# max1k.net
KiCad netlist of a schematic drawn in EAGLE
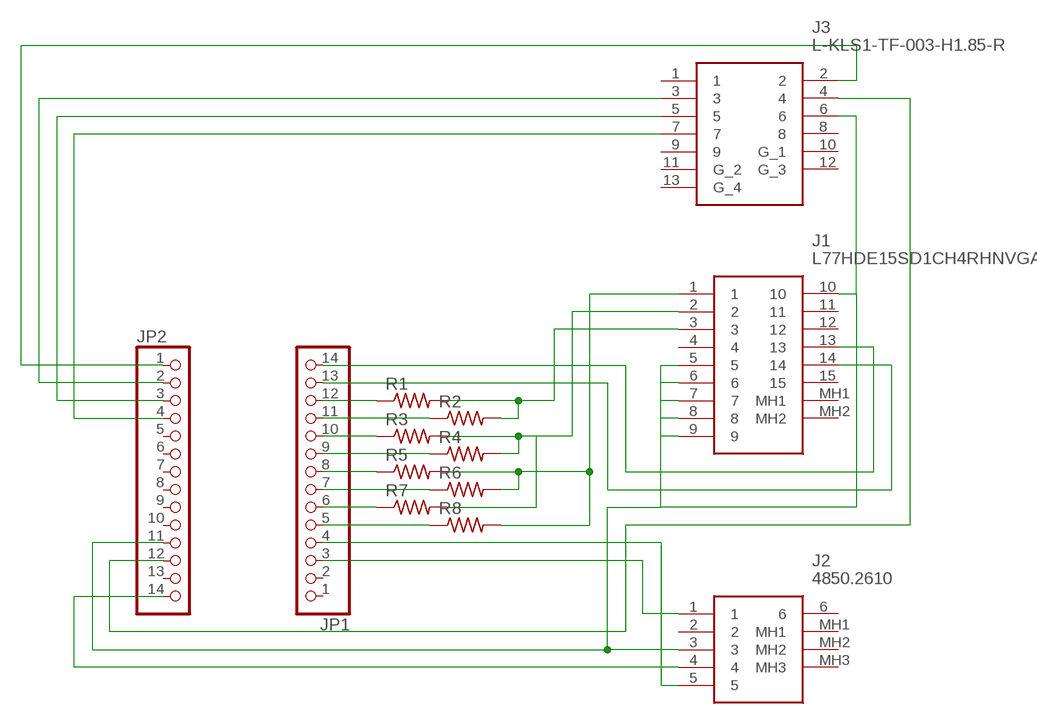
[diagram p0: schematic, sheet 1]

(export (version "E")
  (design (tool "Eeschema 10.0.6"))
  (components
    (comp (ref "J1")
      (value "L77HDE15SD1CH4RHNVGA")
      (footprint "eagle-import:L77HDE15SD1CH4RHNVGA")
      (fields (field (name "MOUSER_PART_NUMBER") "523-7HDE15SDH4RHNVGA"))
      (libsource (lib "eagle-import") (part "L77HDE15SD1CH4RHNVGA"))
    )
    (comp (ref "J2")
      (value "4850.2610")
      (footprint "eagle-import:48502610")
      (fields (field (name "MOUSER_PART_NUMBER") "693-4850.2610"))
      (libsource (lib "eagle-import") (part "4850.2610"))
    )
    (comp (ref "J3")
      (value "L-KLS1-TF-003-H1.85-R")
      (footprint "eagle-import:L-KLS1-TF-003-H1.85-R")
      (libsource (lib "eagle-import") (part "L-KLS1-TF-003-H1.85-R"))
    )
    (comp (ref "JP1")
      (value "PINHD-1X14-CB")
      (footprint "eagle-import:1X14-CB")
      (libsource (lib "eagle-import") (part "PINHD-1X14-CB"))
    )
    (comp (ref "JP2")
      (value "PINHD-1X14-CB")
      (footprint "eagle-import:1X14-CB")
      (libsource (lib "eagle-import") (part "PINHD-1X14-CB"))
    )
    (comp (ref "R1")
      (value "R-US_R0805")
      (footprint "eagle-import:R0805")
      (libsource (lib "eagle-import") (part "R-US_R0805"))
    )
    (comp (ref "R2")
      (value "R-US_R0805")
      (footprint "eagle-import:R0805")
      (libsource (lib "eagle-import") (part "R-US_R0805"))
    )
    (comp (ref "R3")
      (value "R-US_R0805")
      (footprint "eagle-import:R0805")
      (libsource (lib "eagle-import") (part "R-US_R0805"))
    )
    (comp (ref "R4")
      (value "R-US_R0805")
      (footprint "eagle-import:R0805")
      (libsource (lib "eagle-import") (part "R-US_R0805"))
    )
    (comp (ref "R5")
      (value "R-US_R0805")
      (footprint "eagle-import:R0805")
      (libsource (lib "eagle-import") (part "R-US_R0805"))
    )
    (comp (ref "R6")
      (value "R-US_R0805")
      (footprint "eagle-import:R0805")
      (libsource (lib "eagle-import") (part "R-US_R0805"))
    )
    (comp (ref "R7")
      (value "R-US_R0805")
      (footprint "eagle-import:R0805")
      (libsource (lib "eagle-import") (part "R-US_R0805"))
    )
    (comp (ref "R8")
      (value "R-US_R0805")
      (footprint "eagle-import:R0805")
      (libsource (lib "eagle-import") (part "R-US_R0805"))
    )
  )
  (nets
    (net (code "1") (name "Net-(J1-Pad1)") (class "Default")
      (node (ref "J1") (pin "1") (pinfunction "1_1") (pintype "bidirectional"))
      (node (ref "R5") (pin "2") (pinfunction "2_2") (pintype "passive"))
      (node (ref "R6") (pin "2") (pinfunction "2_2") (pintype "passive"))
      (node (ref "R8") (pin "2") (pinfunction "2_2") (pintype "passive"))
    )
    (net (code "2") (name "Net-(J1-Pad2)") (class "Default")
      (node (ref "J1") (pin "2") (pinfunction "2_2") (pintype "bidirectional"))
      (node (ref "R3") (pin "2") (pinfunction "2_2") (pintype "passive"))
      (node (ref "R4") (pin "2") (pinfunction "2_2") (pintype "passive"))
      (node (ref "R7") (pin "2") (pinfunction "2_2") (pintype "passive"))
    )
    (net (code "3") (name "Net-(J1-Pad3)") (class "Default")
      (node (ref "J1") (pin "3") (pinfunction "3_3") (pintype "bidirectional"))
      (node (ref "R1") (pin "2") (pinfunction "2_2") (pintype "passive"))
      (node (ref "R2") (pin "2") (pinfunction "2_2") (pintype "passive"))
    )
    (net (code "4") (name "Net-(J1-Pad10)") (class "Default")
      (node (ref "J1") (pin "10") (pinfunction "10_10") (pintype "bidirectional"))
      (node (ref "J1") (pin "5") (pinfunction "5_5") (pintype "bidirectional"))
      (node (ref "J1") (pin "6") (pinfunction "6_6") (pintype "bidirectional"))
      (node (ref "J1") (pin "7") (pinfunction "7_7") (pintype "bidirectional"))
      (node (ref "J1") (pin "8") (pinfunction "8_8") (pintype "bidirectional"))
      (node (ref "J1") (pin "9") (pinfunction "9_9") (pintype "bidirectional"))
      (node (ref "J2") (pin "3") (pinfunction "3_3") (pintype "bidirectional"))
      (node (ref "J3") (pin "6") (pinfunction "6_6") (pintype "bidirectional"))
      (node (ref "JP2") (pin "11") (pinfunction "11_11") (pintype "passive"))
    )
    (net (code "5") (name "Net-(J1-Pad13)") (class "Default")
      (node (ref "J1") (pin "13") (pinfunction "13_13") (pintype "bidirectional"))
      (node (ref "JP1") (pin "14") (pinfunction "14_14") (pintype "passive"))
    )
    (net (code "6") (name "Net-(J1-Pad14)") (class "Default")
      (node (ref "J1") (pin "14") (pinfunction "14_14") (pintype "bidirectional"))
      (node (ref "JP1") (pin "13") (pinfunction "13_13") (pintype "passive"))
    )
    (net (code "7") (name "Net-(J2-Pad1)") (class "Default")
      (node (ref "J2") (pin "1") (pinfunction "1_1") (pintype "bidirectional"))
      (node (ref "JP1") (pin "3") (pinfunction "3_3") (pintype "passive"))
    )
    (net (code "8") (name "Net-(J2-Pad4)") (class "Default")
      (node (ref "J2") (pin "4") (pinfunction "4_4") (pintype "bidirectional"))
      (node (ref "JP2") (pin "14") (pinfunction "14_14") (pintype "passive"))
    )
    (net (code "9") (name "Net-(J2-Pad5)") (class "Default")
      (node (ref "J2") (pin "5") (pinfunction "5_5") (pintype "bidirectional"))
      (node (ref "JP1") (pin "4") (pinfunction "4_4") (pintype "passive"))
    )
    (net (code "10") (name "Net-(J3-Pad2)") (class "Default")
      (node (ref "J3") (pin "2") (pinfunction "2_2") (pintype "bidirectional"))
      (node (ref "JP2") (pin "1") (pinfunction "1_1") (pintype "passive"))
    )
    (net (code "11") (name "Net-(J3-Pad3)") (class "Default")
      (node (ref "J3") (pin "3") (pinfunction "3_3") (pintype "bidirectional"))
      (node (ref "JP2") (pin "2") (pinfunction "2_2") (pintype "passive"))
    )
    (net (code "12") (name "Net-(J3-Pad4)") (class "Default")
      (node (ref "J3") (pin "4") (pinfunction "4_4") (pintype "bidirectional"))
      (node (ref "JP2") (pin "12") (pinfunction "12_12") (pintype "passive"))
    )
    (net (code "13") (name "Net-(J3-Pad5)") (class "Default")
      (node (ref "J3") (pin "5") (pinfunction "5_5") (pintype "bidirectional"))
      (node (ref "JP2") (pin "3") (pinfunction "3_3") (pintype "passive"))
    )
    (net (code "14") (name "Net-(J3-Pad7)") (class "Default")
      (node (ref "J3") (pin "7") (pinfunction "7_7") (pintype "bidirectional"))
      (node (ref "JP2") (pin "4") (pinfunction "4_4") (pintype "passive"))
    )
    (net (code "15") (name "Net-(JP1-Pad5)") (class "Default")
      (node (ref "JP1") (pin "5") (pinfunction "5_5") (pintype "passive"))
      (node (ref "R8") (pin "1") (pinfunction "1_1") (pintype "passive"))
    )
    (net (code "16") (name "Net-(JP1-Pad6)") (class "Default")
      (node (ref "JP1") (pin "6") (pinfunction "6_6") (pintype "passive"))
      (node (ref "R7") (pin "1") (pinfunction "1_1") (pintype "passive"))
    )
    (net (code "17") (name "Net-(JP1-Pad7)") (class "Default")
      (node (ref "JP1") (pin "7") (pinfunction "7_7") (pintype "passive"))
      (node (ref "R6") (pin "1") (pinfunction "1_1") (pintype "passive"))
    )
    (net (code "18") (name "Net-(JP1-Pad8)") (class "Default")
      (node (ref "JP1") (pin "8") (pinfunction "8_8") (pintype "passive"))
      (node (ref "R5") (pin "1") (pinfunction "1_1") (pintype "passive"))
    )
    (net (code "19") (name "Net-(JP1-Pad9)") (class "Default")
      (node (ref "JP1") (pin "9") (pinfunction "9_9") (pintype "passive"))
      (node (ref "R4") (pin "1") (pinfunction "1_1") (pintype "passive"))
    )
    (net (code "20") (name "Net-(JP1-Pad10)") (class "Default")
      (node (ref "JP1") (pin "10") (pinfunction "10_10") (pintype "passive"))
      (node (ref "R3") (pin "1") (pinfunction "1_1") (pintype "passive"))
    )
    (net (code "21") (name "Net-(JP1-Pad11)") (class "Default")
      (node (ref "JP1") (pin "11") (pinfunction "11_11") (pintype "passive"))
      (node (ref "R2") (pin "1") (pinfunction "1_1") (pintype "passive"))
    )
    (net (code "22") (name "Net-(JP1-Pad12)") (class "Default")
      (node (ref "JP1") (pin "12") (pinfunction "12_12") (pintype "passive"))
      (node (ref "R1") (pin "1") (pinfunction "1_1") (pintype "passive"))
    )
    (net (code "23") (name "unconnected-(J1-Pad4)") (class "Default")
      (node (ref "J1") (pin "4") (pinfunction "4_4") (pintype "bidirectional"))
    )
    (net (code "24") (name "unconnected-(J1-Pad11)") (class "Default")
      (node (ref "J1") (pin "11") (pinfunction "11_11") (pintype "bidirectional"))
    )
    (net (code "25") (name "unconnected-(J1-Pad12)") (class "Default")
      (node (ref "J1") (pin "12") (pinfunction "12_12") (pintype "bidirectional"))
    )
    (net (code "26") (name "unconnected-(J1-Pad15)") (class "Default")
      (node (ref "J1") (pin "15") (pinfunction "15_15") (pintype "bidirectional"))
    )
    (net (code "27") (name "unconnected-(J1-PadMH1)") (class "Default")
      (node (ref "J1") (pin "MH1") (pinfunction "MH1_MH1") (pintype "bidirectional"))
    )
    (net (code "28") (name "unconnected-(J1-PadMH2)") (class "Default")
      (node (ref "J1") (pin "MH2") (pinfunction "MH2_MH2") (pintype "bidirectional"))
    )
    (net (code "29") (name "unconnected-(J2-Pad2)") (class "Default")
      (node (ref "J2") (pin "2") (pinfunction "2_2") (pintype "bidirectional"))
    )
    (net (code "30") (name "unconnected-(J2-Pad6)") (class "Default")
      (node (ref "J2") (pin "6") (pinfunction "6_6") (pintype "bidirectional"))
    )
    (net (code "31") (name "unconnected-(J2-PadMH1)") (class "Default")
      (node (ref "J2") (pin "MH1") (pinfunction "MH1_MH1") (pintype "bidirectional"))
    )
    (net (code "32") (name "unconnected-(J2-PadMH2)") (class "Default")
      (node (ref "J2") (pin "MH2") (pinfunction "MH2_MH2") (pintype "bidirectional"))
    )
    (net (code "33") (name "unconnected-(J2-PadMH3)") (class "Default")
      (node (ref "J2") (pin "MH3") (pinfunction "MH3_MH3") (pintype "bidirectional"))
    )
    (net (code "34") (name "unconnected-(J3-G_1-Pad10)") (class "Default")
      (node (ref "J3") (pin "10") (pinfunction "G_1_10") (pintype "bidirectional"))
    )
    (net (code "35") (name "unconnected-(J3-G_2-Pad11)") (class "Default")
      (node (ref "J3") (pin "11") (pinfunction "G_2_11") (pintype "bidirectional"))
    )
    (net (code "36") (name "unconnected-(J3-G_3-Pad12)") (class "Default")
      (node (ref "J3") (pin "12") (pinfunction "G_3_12") (pintype "bidirectional"))
    )
    (net (code "37") (name "unconnected-(J3-G_4-Pad13)") (class "Default")
      (node (ref "J3") (pin "13") (pinfunction "G_4_13") (pintype "bidirectional"))
    )
    (net (code "38") (name "unconnected-(J3-Pad1)") (class "Default")
      (node (ref "J3") (pin "1") (pinfunction "1_1") (pintype "bidirectional"))
    )
    (net (code "39") (name "unconnected-(J3-Pad8)") (class "Default")
      (node (ref "J3") (pin "8") (pinfunction "8_8") (pintype "bidirectional"))
    )
    (net (code "40") (name "unconnected-(J3-Pad9)") (class "Default")
      (node (ref "J3") (pin "9") (pinfunction "9_9") (pintype "bidirectional"))
    )
    (net (code "41") (name "unconnected-(JP1-Pad1)") (class "Default")
      (node (ref "JP1") (pin "1") (pinfunction "1_1") (pintype "passive"))
    )
    (net (code "42") (name "unconnected-(JP1-Pad2)") (class "Default")
      (node (ref "JP1") (pin "2") (pinfunction "2_2") (pintype "passive"))
    )
    (net (code "43") (name "unconnected-(JP2-Pad5)") (class "Default")
      (node (ref "JP2") (pin "5") (pinfunction "5_5") (pintype "passive"))
    )
    (net (code "44") (name "unconnected-(JP2-Pad6)") (class "Default")
      (node (ref "JP2") (pin "6") (pinfunction "6_6") (pintype "passive"))
    )
    (net (code "45") (name "unconnected-(JP2-Pad7)") (class "Default")
      (node (ref "JP2") (pin "7") (pinfunction "7_7") (pintype "passive"))
    )
    (net (code "46") (name "unconnected-(JP2-Pad8)") (class "Default")
      (node (ref "JP2") (pin "8") (pinfunction "8_8") (pintype "passive"))
    )
    (net (code "47") (name "unconnected-(JP2-Pad9)") (class "Default")
      (node (ref "JP2") (pin "9") (pinfunction "9_9") (pintype "passive"))
    )
    (net (code "48") (name "unconnected-(JP2-Pad10)") (class "Default")
      (node (ref "JP2") (pin "10") (pinfunction "10_10") (pintype "passive"))
    )
    (net (code "49") (name "unconnected-(JP2-Pad13)") (class "Default")
      (node (ref "JP2") (pin "13") (pinfunction "13_13") (pintype "passive"))
    )
  )
)
